# Comparator_1_1.net
KiCad netlist of a schematic drawn in EAGLE
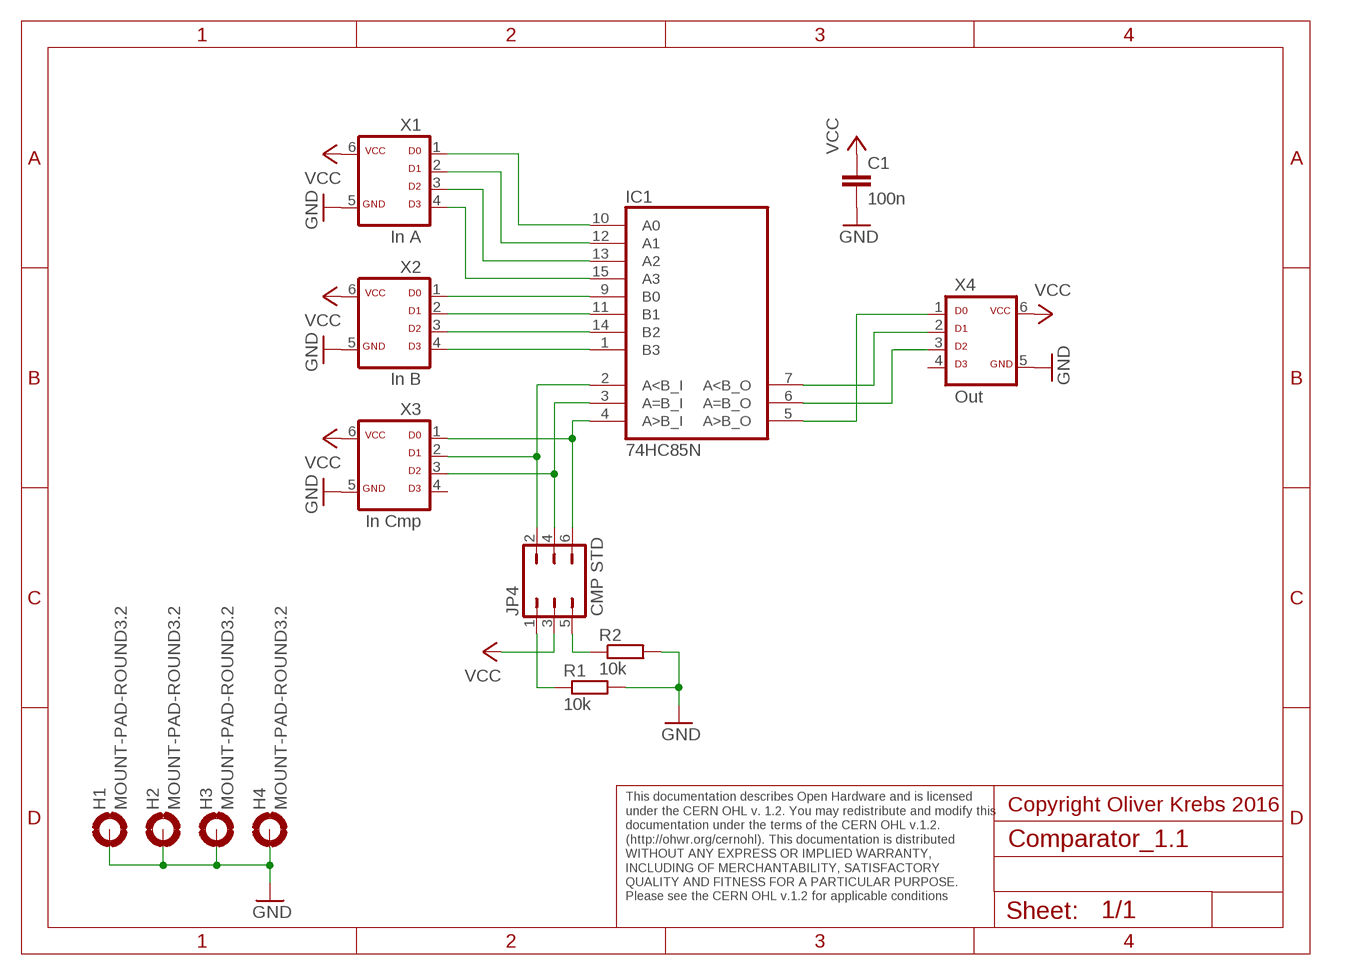
[diagram p0: schematic, sheet 1]

(export (version "E")
  (design (tool "Eeschema 10.0.6"))
  (components
    (comp (ref "C1")
      (value "100n")
      (footprint "eagle-import:C050-025X075")
      (libsource (lib "eagle-import") (part "C-EU050-025X075"))
    )
    (comp (ref "H1")
      (value "MOUNT-PAD-ROUND3.2")
      (footprint "eagle-import:3,2-PAD")
      (libsource (lib "eagle-import") (part "MOUNT-PAD-ROUND3.2"))
    )
    (comp (ref "H2")
      (value "MOUNT-PAD-ROUND3.2")
      (footprint "eagle-import:3,2-PAD")
      (libsource (lib "eagle-import") (part "MOUNT-PAD-ROUND3.2"))
    )
    (comp (ref "H3")
      (value "MOUNT-PAD-ROUND3.2")
      (footprint "eagle-import:3,2-PAD")
      (libsource (lib "eagle-import") (part "MOUNT-PAD-ROUND3.2"))
    )
    (comp (ref "H4")
      (value "MOUNT-PAD-ROUND3.2")
      (footprint "eagle-import:3,2-PAD")
      (libsource (lib "eagle-import") (part "MOUNT-PAD-ROUND3.2"))
    )
    (comp (ref "IC1")
      (value "74HC85N")
      (footprint "eagle-import:DIL16")
      (libsource (lib "eagle-import") (part "7485NHC"))
    )
    (comp (ref "JP4")
      (value "CMP STD")
      (footprint "eagle-import:JP3Q")
      (libsource (lib "eagle-import") (part "JP3Q"))
    )
    (comp (ref "R1")
      (value "10k")
      (footprint "eagle-import:0207_10")
      (libsource (lib "eagle-import") (part "R-EU_0207/10"))
    )
    (comp (ref "R2")
      (value "10k")
      (footprint "eagle-import:0207_10")
      (libsource (lib "eagle-import") (part "R-EU_0207/10"))
    )
    (comp (ref "X1")
      (value "In A")
      (footprint "eagle-import:ML-6")
      (libsource (lib "eagle-import") (part "ML6D"))
    )
    (comp (ref "X2")
      (value "In B")
      (footprint "eagle-import:ML-6")
      (libsource (lib "eagle-import") (part "ML6D"))
    )
    (comp (ref "X3")
      (value "In Cmp")
      (footprint "eagle-import:ML-6")
      (libsource (lib "eagle-import") (part "ML6D"))
    )
    (comp (ref "X4")
      (value "Out")
      (footprint "eagle-import:ML-6")
      (libsource (lib "eagle-import") (part "ML6D"))
    )
  )
  (nets
    (net (code "1") (name "GND") (class "Default")
      (node (ref "C1") (pin "2") (pinfunction "2_2") (pintype "passive"))
      (node (ref "H1") (pin "B3,2") (pinfunction "MOUNT_B3,2") (pintype "passive"))
      (node (ref "H2") (pin "B3,2") (pinfunction "MOUNT_B3,2") (pintype "passive"))
      (node (ref "H3") (pin "B3,2") (pinfunction "MOUNT_B3,2") (pintype "passive"))
      (node (ref "H4") (pin "B3,2") (pinfunction "MOUNT_B3,2") (pintype "passive"))
      (node (ref "R1") (pin "2") (pinfunction "2_2") (pintype "passive"))
      (node (ref "R2") (pin "2") (pinfunction "2_2") (pintype "passive"))
      (node (ref "X1") (pin "5") (pinfunction "5_5") (pintype "passive"))
      (node (ref "X2") (pin "5") (pinfunction "5_5") (pintype "passive"))
      (node (ref "X3") (pin "5") (pinfunction "5_5") (pintype "passive"))
      (node (ref "X4") (pin "5") (pinfunction "5_5") (pintype "passive"))
    )
    (net (code "2") (name "Net-(IC1A-A0)") (class "Default")
      (node (ref "IC1") (pin "10") (pinfunction "A0_10") (pintype "input"))
      (node (ref "X1") (pin "1") (pinfunction "1_1") (pintype "passive"))
    )
    (net (code "3") (name "Net-(IC1A-A1)") (class "Default")
      (node (ref "IC1") (pin "12") (pinfunction "A1_12") (pintype "input"))
      (node (ref "X1") (pin "2") (pinfunction "2_2") (pintype "passive"))
    )
    (net (code "4") (name "Net-(IC1A-A2)") (class "Default")
      (node (ref "IC1") (pin "13") (pinfunction "A2_13") (pintype "input"))
      (node (ref "X1") (pin "3") (pinfunction "3_3") (pintype "passive"))
    )
    (net (code "5") (name "Net-(IC1A-A3)") (class "Default")
      (node (ref "IC1") (pin "15") (pinfunction "A3_15") (pintype "input"))
      (node (ref "X1") (pin "4") (pinfunction "4_4") (pintype "passive"))
    )
    (net (code "6") (name "Net-(IC1A-A<B_I)") (class "Default")
      (node (ref "IC1") (pin "2") (pinfunction "A<B_I_2") (pintype "input"))
      (node (ref "JP4") (pin "2") (pinfunction "2_2") (pintype "passive"))
      (node (ref "X3") (pin "2") (pinfunction "2_2") (pintype "passive"))
    )
    (net (code "7") (name "Net-(IC1A-A<B_O)") (class "Default")
      (node (ref "IC1") (pin "7") (pinfunction "A<B_O_7") (pintype "output"))
      (node (ref "X4") (pin "2") (pinfunction "2_2") (pintype "passive"))
    )
    (net (code "8") (name "Net-(IC1A-A=B_I)") (class "Default")
      (node (ref "IC1") (pin "3") (pinfunction "A=B_I_3") (pintype "input"))
      (node (ref "JP4") (pin "4") (pinfunction "4_4") (pintype "passive"))
      (node (ref "X3") (pin "3") (pinfunction "3_3") (pintype "passive"))
    )
    (net (code "9") (name "Net-(IC1A-A=B_O)") (class "Default")
      (node (ref "IC1") (pin "6") (pinfunction "A=B_O_6") (pintype "output"))
      (node (ref "X4") (pin "3") (pinfunction "3_3") (pintype "passive"))
    )
    (net (code "10") (name "Net-(IC1A-A>B_I)") (class "Default")
      (node (ref "IC1") (pin "4") (pinfunction "A>B_I_4") (pintype "input"))
      (node (ref "JP4") (pin "6") (pinfunction "6_6") (pintype "passive"))
      (node (ref "X3") (pin "1") (pinfunction "1_1") (pintype "passive"))
    )
    (net (code "11") (name "Net-(IC1A-A>B_O)") (class "Default")
      (node (ref "IC1") (pin "5") (pinfunction "A>B_O_5") (pintype "output"))
      (node (ref "X4") (pin "1") (pinfunction "1_1") (pintype "passive"))
    )
    (net (code "12") (name "Net-(IC1A-B0)") (class "Default")
      (node (ref "IC1") (pin "9") (pinfunction "B0_9") (pintype "input"))
      (node (ref "X2") (pin "1") (pinfunction "1_1") (pintype "passive"))
    )
    (net (code "13") (name "Net-(IC1A-B1)") (class "Default")
      (node (ref "IC1") (pin "11") (pinfunction "B1_11") (pintype "input"))
      (node (ref "X2") (pin "2") (pinfunction "2_2") (pintype "passive"))
    )
    (net (code "14") (name "Net-(IC1A-B2)") (class "Default")
      (node (ref "IC1") (pin "14") (pinfunction "B2_14") (pintype "input"))
      (node (ref "X2") (pin "3") (pinfunction "3_3") (pintype "passive"))
    )
    (net (code "15") (name "Net-(IC1A-B3)") (class "Default")
      (node (ref "IC1") (pin "1") (pinfunction "B3_1") (pintype "input"))
      (node (ref "X2") (pin "4") (pinfunction "4_4") (pintype "passive"))
    )
    (net (code "16") (name "Net-(JP4-Pad1)") (class "Default")
      (node (ref "JP4") (pin "1") (pinfunction "1_1") (pintype "passive"))
      (node (ref "R1") (pin "1") (pinfunction "1_1") (pintype "passive"))
    )
    (net (code "17") (name "Net-(JP4-Pad5)") (class "Default")
      (node (ref "JP4") (pin "5") (pinfunction "5_5") (pintype "passive"))
      (node (ref "R2") (pin "1") (pinfunction "1_1") (pintype "passive"))
    )
    (net (code "18") (name "VCC") (class "Default")
      (node (ref "C1") (pin "1") (pinfunction "1_1") (pintype "passive"))
      (node (ref "JP4") (pin "3") (pinfunction "3_3") (pintype "passive"))
      (node (ref "X1") (pin "6") (pinfunction "6_6") (pintype "passive"))
      (node (ref "X2") (pin "6") (pinfunction "6_6") (pintype "passive"))
      (node (ref "X3") (pin "6") (pinfunction "6_6") (pintype "passive"))
      (node (ref "X4") (pin "6") (pinfunction "6_6") (pintype "passive"))
    )
    (net (code "19") (name "unconnected-(X3-Pad4)") (class "Default")
      (node (ref "X3") (pin "4") (pinfunction "4_4") (pintype "passive"))
    )
    (net (code "20") (name "unconnected-(X4-Pad4)") (class "Default")
      (node (ref "X4") (pin "4") (pinfunction "4_4") (pintype "passive"))
    )
  )
)
